# motor_mbed.net
KiCad netlist of a schematic drawn in EAGLE
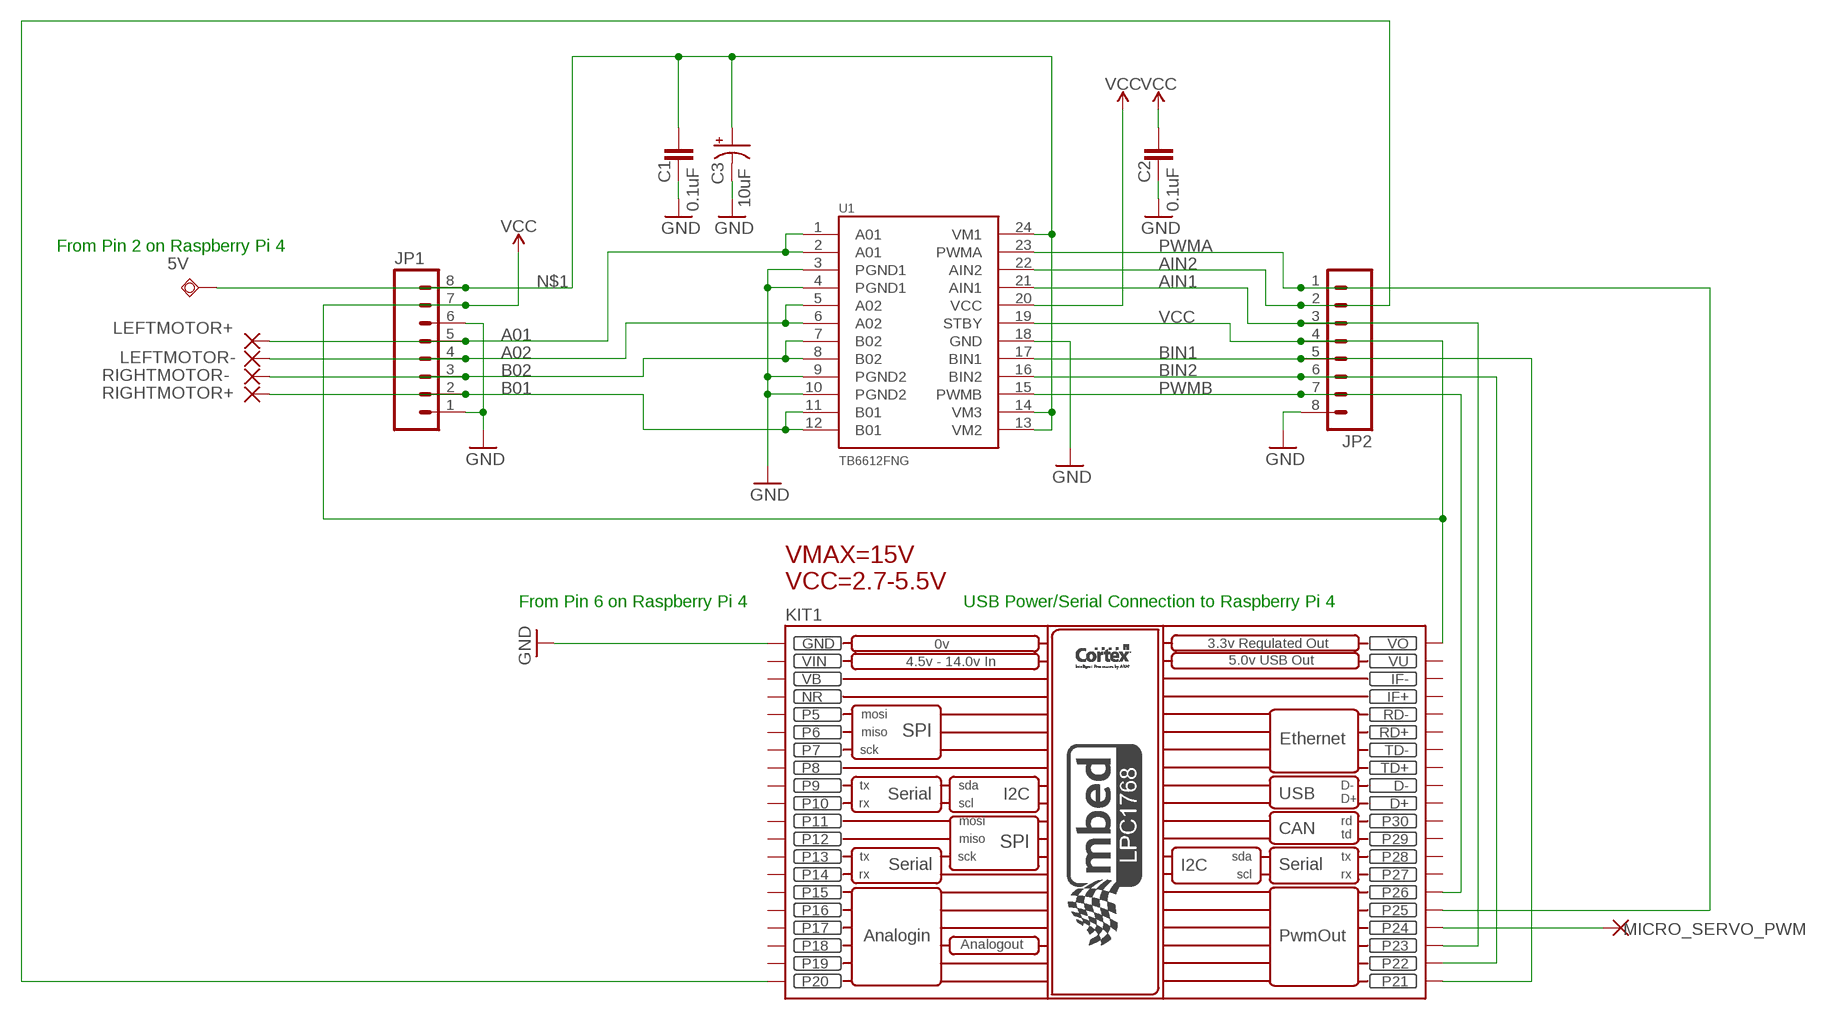
[diagram p0: schematic, sheet 1]

(export (version "E")
  (design (tool "Eeschema 10.0.6"))
  (components
    (comp (ref "5V")
      (value "TPSQPAD1-20")
      (footprint "eagle-import:P1-20")
      (libsource (lib "eagle-import") (part "TPSQPAD1-20"))
    )
    (comp (ref "C1")
      (value "0.1uF")
      (footprint "eagle-import:0402")
      (libsource (lib "eagle-import") (part "0.1UF-0402-16V-10%"))
    )
    (comp (ref "C2")
      (value "0.1uF")
      (footprint "eagle-import:0402")
      (libsource (lib "eagle-import") (part "0.1UF-0402-16V-10%"))
    )
    (comp (ref "C3")
      (value "10uF")
      (footprint "eagle-import:EIA3528")
      (libsource (lib "eagle-import") (part "10UF-POLAR-EIA3528-20V-10%(TANT)"))
    )
    (comp (ref "JP1")
      (value "M0875_PERCENT_REDUCED")
      (footprint "eagle-import:1X08_OFFSET_REDUCED")
      (libsource (lib "eagle-import") (part "M0875_PERCENT_REDUCED"))
    )
    (comp (ref "JP2")
      (value "M0875_PERCENT_REDUCED")
      (footprint "eagle-import:1X08_OFFSET_REDUCED")
      (libsource (lib "eagle-import") (part "M0875_PERCENT_REDUCED"))
    )
    (comp (ref "KIT1")
      (value "MBED_NXP_LPC1768")
      (footprint "eagle-import:MBED-KIT")
      (libsource (lib "eagle-import") (part "MBED_NXP_LPC1768"))
    )
    (comp (ref "LEFTMOTOR+")
      (value "WIREPAD2,54/1,1")
      (footprint "eagle-import:2,54_1,1")
      (libsource (lib "eagle-import") (part "WIREPAD2,54/1,1"))
    )
    (comp (ref "LEFTMOTOR-")
      (value "WIREPAD2,54/1,1")
      (footprint "eagle-import:2,54_1,1")
      (libsource (lib "eagle-import") (part "WIREPAD2,54/1,1"))
    )
    (comp (ref "MICRO_SERVO_PWM")
      (value "WIREPAD2,54/1,1")
      (footprint "eagle-import:2,54_1,1")
      (libsource (lib "eagle-import") (part "WIREPAD2,54/1,1"))
    )
    (comp (ref "RIGHTMOTOR+")
      (value "WIREPAD2,54/1,1")
      (footprint "eagle-import:2,54_1,1")
      (libsource (lib "eagle-import") (part "WIREPAD2,54/1,1"))
    )
    (comp (ref "RIGHTMOTOR-")
      (value "WIREPAD2,54/1,1")
      (footprint "eagle-import:2,54_1,1")
      (libsource (lib "eagle-import") (part "WIREPAD2,54/1,1"))
    )
    (comp (ref "U1")
      (value "TB6612FNG")
      (footprint "eagle-import:SSOP24")
      (libsource (lib "eagle-import") (part "TB6612FNG"))
    )
  )
  (nets
    (net (code "1") (name "/A01") (class "Default")
      (node (ref "JP1") (pin "5") (pinfunction "5_5") (pintype "passive"))
      (node (ref "LEFTMOTOR+") (pin "1") (pinfunction "P_1") (pintype "passive"))
      (node (ref "U1") (pin "1") (pinfunction "A01_1") (pintype "bidirectional"))
      (node (ref "U1") (pin "2") (pinfunction "A01_2") (pintype "bidirectional"))
    )
    (net (code "2") (name "/A02") (class "Default")
      (node (ref "JP1") (pin "4") (pinfunction "4_4") (pintype "passive"))
      (node (ref "LEFTMOTOR-") (pin "1") (pinfunction "P_1") (pintype "passive"))
      (node (ref "U1") (pin "5") (pinfunction "A02_5") (pintype "bidirectional"))
      (node (ref "U1") (pin "6") (pinfunction "A02_6") (pintype "bidirectional"))
    )
    (net (code "3") (name "/AIN1") (class "Default")
      (node (ref "JP2") (pin "3") (pinfunction "3_3") (pintype "passive"))
      (node (ref "KIT1") (pin "P$23") (pinfunction "P23_P$23") (pintype "bidirectional"))
      (node (ref "U1") (pin "21") (pinfunction "AIN1_21") (pintype "bidirectional"))
    )
    (net (code "4") (name "/AIN2") (class "Default")
      (node (ref "JP2") (pin "2") (pinfunction "2_2") (pintype "passive"))
      (node (ref "KIT1") (pin "P$20") (pinfunction "P20_P$20") (pintype "bidirectional"))
      (node (ref "U1") (pin "22") (pinfunction "AIN2_22") (pintype "bidirectional"))
    )
    (net (code "5") (name "/B01") (class "Default")
      (node (ref "JP1") (pin "2") (pinfunction "2_2") (pintype "passive"))
      (node (ref "RIGHTMOTOR+") (pin "1") (pinfunction "P_1") (pintype "passive"))
      (node (ref "U1") (pin "11") (pinfunction "B01_11") (pintype "bidirectional"))
      (node (ref "U1") (pin "12") (pinfunction "B01_12") (pintype "bidirectional"))
    )
    (net (code "6") (name "/B02") (class "Default")
      (node (ref "JP1") (pin "3") (pinfunction "3_3") (pintype "passive"))
      (node (ref "RIGHTMOTOR-") (pin "1") (pinfunction "P_1") (pintype "passive"))
      (node (ref "U1") (pin "7") (pinfunction "B02_7") (pintype "bidirectional"))
      (node (ref "U1") (pin "8") (pinfunction "B02_8") (pintype "bidirectional"))
    )
    (net (code "7") (name "/BIN1") (class "Default")
      (node (ref "JP2") (pin "5") (pinfunction "5_5") (pintype "passive"))
      (node (ref "KIT1") (pin "P$21") (pinfunction "P21_P$21") (pintype "bidirectional"))
      (node (ref "U1") (pin "17") (pinfunction "BIN1_17") (pintype "bidirectional"))
    )
    (net (code "8") (name "/BIN2") (class "Default")
      (node (ref "JP2") (pin "6") (pinfunction "6_6") (pintype "passive"))
      (node (ref "KIT1") (pin "P$22") (pinfunction "P22_P$22") (pintype "bidirectional"))
      (node (ref "U1") (pin "16") (pinfunction "BIN2_16") (pintype "bidirectional"))
    )
    (net (code "9") (name "/N$1") (class "Default")
      (node (ref "5V") (pin "TP") (pinfunction "TP_TP") (pintype "input"))
      (node (ref "C1") (pin "1") (pinfunction "1_1") (pintype "passive"))
      (node (ref "C3") (pin "A") (pinfunction "+_A") (pintype "passive"))
      (node (ref "JP1") (pin "8") (pinfunction "8_8") (pintype "passive"))
      (node (ref "U1") (pin "13") (pinfunction "VM2_13") (pintype "bidirectional"))
      (node (ref "U1") (pin "14") (pinfunction "VM3_14") (pintype "bidirectional"))
      (node (ref "U1") (pin "24") (pinfunction "VM1_24") (pintype "bidirectional"))
    )
    (net (code "10") (name "/NR") (class "Default")
      (node (ref "KIT1") (pin "NR") (pinfunction "NR_NR") (pintype "power_in"))
    )
    (net (code "11") (name "/PWMA") (class "Default")
      (node (ref "JP2") (pin "1") (pinfunction "1_1") (pintype "passive"))
      (node (ref "KIT1") (pin "P$25") (pinfunction "P25_P$25") (pintype "bidirectional"))
      (node (ref "U1") (pin "23") (pinfunction "PWMA_23") (pintype "bidirectional"))
    )
    (net (code "12") (name "/PWMB") (class "Default")
      (node (ref "JP2") (pin "7") (pinfunction "7_7") (pintype "passive"))
      (node (ref "KIT1") (pin "P$26") (pinfunction "P26_P$26") (pintype "bidirectional"))
      (node (ref "U1") (pin "15") (pinfunction "PWMB_15") (pintype "bidirectional"))
    )
    (net (code "13") (name "/VB") (class "Default")
      (node (ref "KIT1") (pin "VB") (pinfunction "VB_VB") (pintype "power_in"))
    )
    (net (code "14") (name "/VIN") (class "Default")
      (node (ref "KIT1") (pin "VIN") (pinfunction "VIN_VIN") (pintype "power_in"))
    )
    (net (code "15") (name "/VU") (class "Default")
      (node (ref "KIT1") (pin "VU") (pinfunction "VU_VU") (pintype "power_in"))
    )
    (net (code "16") (name "GND") (class "Default")
      (node (ref "C1") (pin "2") (pinfunction "2_2") (pintype "passive"))
      (node (ref "C2") (pin "2") (pinfunction "2_2") (pintype "passive"))
      (node (ref "C3") (pin "C") (pinfunction "-_C") (pintype "passive"))
      (node (ref "JP1") (pin "1") (pinfunction "1_1") (pintype "passive"))
      (node (ref "JP1") (pin "6") (pinfunction "6_6") (pintype "passive"))
      (node (ref "JP2") (pin "8") (pinfunction "8_8") (pintype "passive"))
      (node (ref "KIT1") (pin "GND") (pinfunction "GND_GND") (pintype "power_in"))
      (node (ref "U1") (pin "10") (pinfunction "PGND2_10") (pintype "bidirectional"))
      (node (ref "U1") (pin "18") (pinfunction "GND_18") (pintype "bidirectional"))
      (node (ref "U1") (pin "3") (pinfunction "PGND1_3") (pintype "bidirectional"))
      (node (ref "U1") (pin "4") (pinfunction "PGND1_4") (pintype "bidirectional"))
      (node (ref "U1") (pin "9") (pinfunction "PGND2_9") (pintype "bidirectional"))
    )
    (net (code "17") (name "Net-(KIT1-P24)") (class "Default")
      (node (ref "KIT1") (pin "P$24") (pinfunction "P24_P$24") (pintype "bidirectional"))
      (node (ref "MICRO_SERVO_PWM") (pin "1") (pinfunction "P_1") (pintype "passive"))
    )
    (net (code "18") (name "VCC") (class "Default")
      (node (ref "C2") (pin "1") (pinfunction "1_1") (pintype "passive"))
      (node (ref "JP1") (pin "7") (pinfunction "7_7") (pintype "passive"))
      (node (ref "JP2") (pin "4") (pinfunction "4_4") (pintype "passive"))
      (node (ref "KIT1") (pin "VOUT") (pinfunction "VO_VOUT") (pintype "power_in"))
      (node (ref "U1") (pin "19") (pinfunction "STBY_19") (pintype "bidirectional"))
      (node (ref "U1") (pin "20") (pinfunction "VCC_20") (pintype "bidirectional"))
    )
    (net (code "19") (name "unconnected-(KIT1-P5-PadP$5)") (class "Default")
      (node (ref "KIT1") (pin "P$5") (pinfunction "P5_P$5") (pintype "bidirectional"))
    )
    (net (code "20") (name "unconnected-(KIT1-P6-PadP$6)") (class "Default")
      (node (ref "KIT1") (pin "P$6") (pinfunction "P6_P$6") (pintype "bidirectional"))
    )
    (net (code "21") (name "unconnected-(KIT1-P7-PadP$7)") (class "Default")
      (node (ref "KIT1") (pin "P$7") (pinfunction "P7_P$7") (pintype "bidirectional"))
    )
    (net (code "22") (name "unconnected-(KIT1-P8-PadP$8)") (class "Default")
      (node (ref "KIT1") (pin "P$8") (pinfunction "P8_P$8") (pintype "bidirectional"))
    )
    (net (code "23") (name "unconnected-(KIT1-P9-PadP$9)") (class "Default")
      (node (ref "KIT1") (pin "P$9") (pinfunction "P9_P$9") (pintype "bidirectional"))
    )
    (net (code "24") (name "unconnected-(KIT1-P10-PadP$10)") (class "Default")
      (node (ref "KIT1") (pin "P$10") (pinfunction "P10_P$10") (pintype "bidirectional"))
    )
    (net (code "25") (name "unconnected-(KIT1-P11-PadP$11)") (class "Default")
      (node (ref "KIT1") (pin "P$11") (pinfunction "P11_P$11") (pintype "bidirectional"))
    )
    (net (code "26") (name "unconnected-(KIT1-P12-PadP$12)") (class "Default")
      (node (ref "KIT1") (pin "P$12") (pinfunction "P12_P$12") (pintype "bidirectional"))
    )
    (net (code "27") (name "unconnected-(KIT1-P13-PadP$13)") (class "Default")
      (node (ref "KIT1") (pin "P$13") (pinfunction "P13_P$13") (pintype "bidirectional"))
    )
    (net (code "28") (name "unconnected-(KIT1-P14-PadP$14)") (class "Default")
      (node (ref "KIT1") (pin "P$14") (pinfunction "P14_P$14") (pintype "bidirectional"))
    )
    (net (code "29") (name "unconnected-(KIT1-P15-PadP$15)") (class "Default")
      (node (ref "KIT1") (pin "P$15") (pinfunction "P15_P$15") (pintype "bidirectional"))
    )
    (net (code "30") (name "unconnected-(KIT1-P16-PadP$16)") (class "Default")
      (node (ref "KIT1") (pin "P$16") (pinfunction "P16_P$16") (pintype "bidirectional"))
    )
    (net (code "31") (name "unconnected-(KIT1-P17-PadP$17)") (class "Default")
      (node (ref "KIT1") (pin "P$17") (pinfunction "P17_P$17") (pintype "bidirectional"))
    )
    (net (code "32") (name "unconnected-(KIT1-P18-PadP$18)") (class "Default")
      (node (ref "KIT1") (pin "P$18") (pinfunction "P18_P$18") (pintype "bidirectional"))
    )
    (net (code "33") (name "unconnected-(KIT1-P19-PadP$19)") (class "Default")
      (node (ref "KIT1") (pin "P$19") (pinfunction "P19_P$19") (pintype "bidirectional"))
    )
    (net (code "34") (name "unconnected-(KIT1-P27-PadP$27)") (class "Default")
      (node (ref "KIT1") (pin "P$27") (pinfunction "P27_P$27") (pintype "bidirectional"))
    )
    (net (code "35") (name "unconnected-(KIT1-P28-PadP$28)") (class "Default")
      (node (ref "KIT1") (pin "P$28") (pinfunction "P28_P$28") (pintype "bidirectional"))
    )
    (net (code "36") (name "unconnected-(KIT1-P29-PadP$29)") (class "Default")
      (node (ref "KIT1") (pin "P$29") (pinfunction "P29_P$29") (pintype "bidirectional"))
    )
    (net (code "37") (name "unconnected-(KIT1-P30-PadP$30)") (class "Default")
      (node (ref "KIT1") (pin "P$30") (pinfunction "P30_P$30") (pintype "bidirectional"))
    )
    (net (code "38") (name "unconnected-(KIT1-PadD+)") (class "Default")
      (node (ref "KIT1") (pin "D+") (pinfunction "D+_D+") (pintype "bidirectional"))
    )
    (net (code "39") (name "unconnected-(KIT1-PadD-)") (class "Default")
      (node (ref "KIT1") (pin "D-") (pinfunction "D-_D-") (pintype "bidirectional"))
    )
    (net (code "40") (name "unconnected-(KIT1-PadIF+)") (class "Default")
      (node (ref "KIT1") (pin "IF+") (pinfunction "IF+_IF+") (pintype "bidirectional"))
    )
    (net (code "41") (name "unconnected-(KIT1-PadIF-)") (class "Default")
      (node (ref "KIT1") (pin "IF-") (pinfunction "IF-_IF-") (pintype "bidirectional"))
    )
    (net (code "42") (name "unconnected-(KIT1-PadRD+)") (class "Default")
      (node (ref "KIT1") (pin "RD+") (pinfunction "RD+_RD+") (pintype "bidirectional"))
    )
    (net (code "43") (name "unconnected-(KIT1-PadRD-)") (class "Default")
      (node (ref "KIT1") (pin "RD-") (pinfunction "RD-_RD-") (pintype "bidirectional"))
    )
    (net (code "44") (name "unconnected-(KIT1-PadTD+)") (class "Default")
      (node (ref "KIT1") (pin "TD+") (pinfunction "TD+_TD+") (pintype "bidirectional"))
    )
    (net (code "45") (name "unconnected-(KIT1-PadTD-)") (class "Default")
      (node (ref "KIT1") (pin "TD-") (pinfunction "TD-_TD-") (pintype "bidirectional"))
    )
  )
)
